# moduloAcionamento.net
KiCad netlist of a schematic drawn in EAGLE
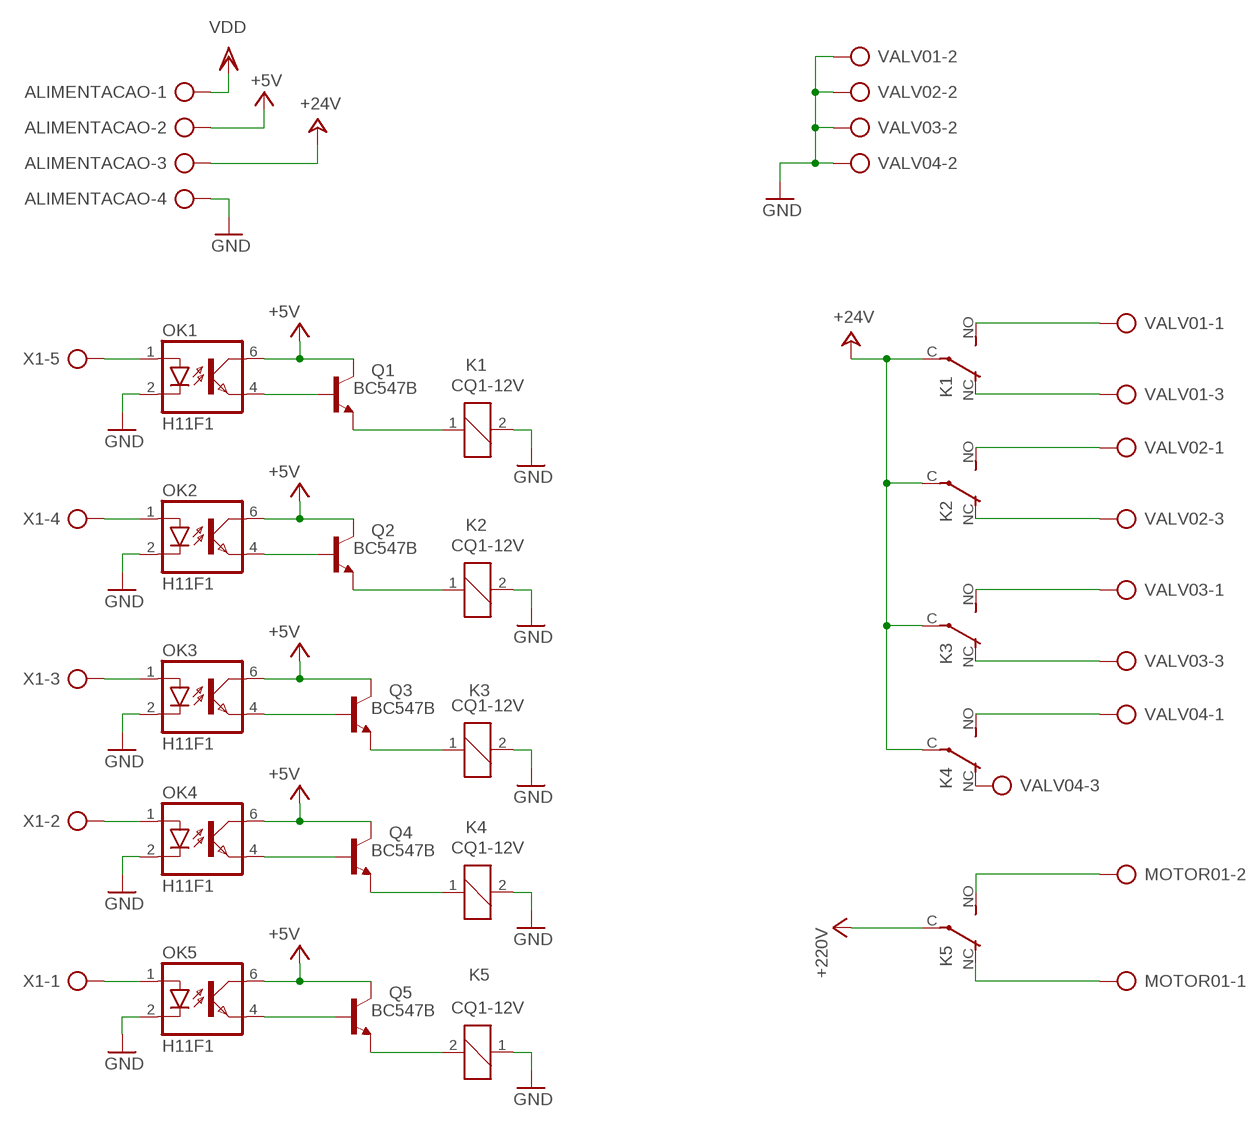
[diagram p0: schematic, sheet 1]

(export (version "E")
  (design (tool "Eeschema 10.0.6"))
  (components
    (comp (ref "ALIMENTACAO")
      (value "AK500/4")
      (footprint "eagle-import:AK500_4")
      (libsource (lib "eagle-import") (part "AK500/4"))
    )
    (comp (ref "K1")
      (value "CQ1-12V")
      (footprint "eagle-import:CQ1")
      (libsource (lib "eagle-import") (part "CQ1-12V"))
    )
    (comp (ref "K2")
      (value "CQ1-12V")
      (footprint "eagle-import:CQ1")
      (libsource (lib "eagle-import") (part "CQ1-12V"))
    )
    (comp (ref "K3")
      (value "CQ1-12V")
      (footprint "eagle-import:CQ1")
      (libsource (lib "eagle-import") (part "CQ1-12V"))
    )
    (comp (ref "K4")
      (value "CQ1-12V")
      (footprint "eagle-import:CQ1")
      (libsource (lib "eagle-import") (part "CQ1-12V"))
    )
    (comp (ref "K5")
      (value "CQ1-12V")
      (footprint "eagle-import:CQ1")
      (libsource (lib "eagle-import") (part "CQ1-12V"))
    )
    (comp (ref "MOTOR01")
      (value "AK500/2")
      (footprint "eagle-import:AK500_2")
      (libsource (lib "eagle-import") (part "AK500/2"))
    )
    (comp (ref "OK1")
      (value "H11F1")
      (footprint "eagle-import:DIL05")
      (libsource (lib "eagle-import") (part "H11F1"))
    )
    (comp (ref "OK2")
      (value "H11F1")
      (footprint "eagle-import:DIL05")
      (libsource (lib "eagle-import") (part "H11F1"))
    )
    (comp (ref "OK3")
      (value "H11F1")
      (footprint "eagle-import:DIL05")
      (libsource (lib "eagle-import") (part "H11F1"))
    )
    (comp (ref "OK4")
      (value "H11F1")
      (footprint "eagle-import:DIL05")
      (libsource (lib "eagle-import") (part "H11F1"))
    )
    (comp (ref "OK5")
      (value "H11F1")
      (footprint "eagle-import:DIL05")
      (libsource (lib "eagle-import") (part "H11F1"))
    )
    (comp (ref "Q1")
      (value "BC547B")
      (footprint "eagle-import:TO92")
      (libsource (lib "eagle-import") (part "BC547B"))
    )
    (comp (ref "Q2")
      (value "BC547B")
      (footprint "eagle-import:TO92")
      (libsource (lib "eagle-import") (part "BC547B"))
    )
    (comp (ref "Q3")
      (value "BC547B")
      (footprint "eagle-import:TO92")
      (libsource (lib "eagle-import") (part "BC547B"))
    )
    (comp (ref "Q4")
      (value "BC547B")
      (footprint "eagle-import:TO92")
      (libsource (lib "eagle-import") (part "BC547B"))
    )
    (comp (ref "Q5")
      (value "BC547B")
      (footprint "eagle-import:TO92")
      (libsource (lib "eagle-import") (part "BC547B"))
    )
    (comp (ref "VALV01")
      (value "AK500/3")
      (footprint "eagle-import:AK500_3")
      (libsource (lib "eagle-import") (part "AK500/3"))
    )
    (comp (ref "VALV02")
      (value "AK500/3")
      (footprint "eagle-import:AK500_3")
      (libsource (lib "eagle-import") (part "AK500/3"))
    )
    (comp (ref "VALV03")
      (value "AK500/3")
      (footprint "eagle-import:AK500_3")
      (libsource (lib "eagle-import") (part "AK500/3"))
    )
    (comp (ref "VALV04")
      (value "AK500/3")
      (footprint "eagle-import:AK500_3")
      (libsource (lib "eagle-import") (part "AK500/3"))
    )
    (comp (ref "X1")
      (value "AK500/5")
      (footprint "eagle-import:AK500_5")
      (libsource (lib "eagle-import") (part "AK500/5"))
    )
  )
  (nets
    (net (code "1") (name "+24V") (class "Default")
      (node (ref "ALIMENTACAO") (pin "3") (pinfunction "KL_3") (pintype "passive"))
      (node (ref "K1") (pin "C") (pinfunction "P_C") (pintype "passive"))
      (node (ref "K2") (pin "C") (pinfunction "P_C") (pintype "passive"))
      (node (ref "K3") (pin "C") (pinfunction "P_C") (pintype "passive"))
      (node (ref "K4") (pin "C") (pinfunction "P_C") (pintype "passive"))
    )
    (net (code "2") (name "+220V") (class "Default")
      (node (ref "ALIMENTACAO") (pin "2") (pinfunction "KL_2") (pintype "passive"))
      (node (ref "K5") (pin "C") (pinfunction "P_C") (pintype "passive"))
      (node (ref "OK1") (pin "6") (pinfunction "COL_6") (pintype "passive"))
      (node (ref "OK2") (pin "6") (pinfunction "COL_6") (pintype "passive"))
      (node (ref "OK3") (pin "6") (pinfunction "COL_6") (pintype "passive"))
      (node (ref "OK4") (pin "6") (pinfunction "COL_6") (pintype "passive"))
      (node (ref "OK5") (pin "6") (pinfunction "COL_6") (pintype "passive"))
      (node (ref "Q1") (pin "3") (pinfunction "C_3") (pintype "passive"))
      (node (ref "Q2") (pin "3") (pinfunction "C_3") (pintype "passive"))
      (node (ref "Q3") (pin "3") (pinfunction "C_3") (pintype "passive"))
      (node (ref "Q4") (pin "3") (pinfunction "C_3") (pintype "passive"))
      (node (ref "Q5") (pin "3") (pinfunction "C_3") (pintype "passive"))
    )
    (net (code "3") (name "GND") (class "Default")
      (node (ref "ALIMENTACAO") (pin "4") (pinfunction "KL_4") (pintype "passive"))
      (node (ref "K1") (pin "2") (pinfunction "2_2") (pintype "passive"))
      (node (ref "K2") (pin "2") (pinfunction "2_2") (pintype "passive"))
      (node (ref "K3") (pin "2") (pinfunction "2_2") (pintype "passive"))
      (node (ref "K4") (pin "2") (pinfunction "2_2") (pintype "passive"))
      (node (ref "K5") (pin "1") (pinfunction "1_1") (pintype "passive"))
      (node (ref "OK1") (pin "2") (pinfunction "C_2") (pintype "passive"))
      (node (ref "OK2") (pin "2") (pinfunction "C_2") (pintype "passive"))
      (node (ref "OK3") (pin "2") (pinfunction "C_2") (pintype "passive"))
      (node (ref "OK4") (pin "2") (pinfunction "C_2") (pintype "passive"))
      (node (ref "OK5") (pin "2") (pinfunction "C_2") (pintype "passive"))
      (node (ref "VALV01") (pin "2") (pinfunction "KL_2") (pintype "passive"))
      (node (ref "VALV02") (pin "2") (pinfunction "KL_2") (pintype "passive"))
      (node (ref "VALV03") (pin "2") (pinfunction "KL_2") (pintype "passive"))
      (node (ref "VALV04") (pin "2") (pinfunction "KL_2") (pintype "passive"))
    )
    (net (code "4") (name "Net-(K1B-O)") (class "Default")
      (node (ref "K1") (pin "NC") (pinfunction "O_NC") (pintype "passive"))
      (node (ref "VALV01") (pin "3") (pinfunction "KL_3") (pintype "passive"))
    )
    (net (code "5") (name "Net-(K1B-S)") (class "Default")
      (node (ref "K1") (pin "NO") (pinfunction "S_NO") (pintype "passive"))
      (node (ref "VALV01") (pin "1") (pinfunction "KL_1") (pintype "passive"))
    )
    (net (code "6") (name "Net-(K2B-O)") (class "Default")
      (node (ref "K2") (pin "NC") (pinfunction "O_NC") (pintype "passive"))
      (node (ref "VALV02") (pin "3") (pinfunction "KL_3") (pintype "passive"))
    )
    (net (code "7") (name "Net-(K2B-S)") (class "Default")
      (node (ref "K2") (pin "NO") (pinfunction "S_NO") (pintype "passive"))
      (node (ref "VALV02") (pin "1") (pinfunction "KL_1") (pintype "passive"))
    )
    (net (code "8") (name "Net-(K3B-O)") (class "Default")
      (node (ref "K3") (pin "NC") (pinfunction "O_NC") (pintype "passive"))
      (node (ref "VALV03") (pin "3") (pinfunction "KL_3") (pintype "passive"))
    )
    (net (code "9") (name "Net-(K3B-S)") (class "Default")
      (node (ref "K3") (pin "NO") (pinfunction "S_NO") (pintype "passive"))
      (node (ref "VALV03") (pin "1") (pinfunction "KL_1") (pintype "passive"))
    )
    (net (code "10") (name "Net-(K4B-O)") (class "Default")
      (node (ref "K4") (pin "NC") (pinfunction "O_NC") (pintype "passive"))
      (node (ref "VALV04") (pin "3") (pinfunction "KL_3") (pintype "passive"))
    )
    (net (code "11") (name "Net-(K4B-S)") (class "Default")
      (node (ref "K4") (pin "NO") (pinfunction "S_NO") (pintype "passive"))
      (node (ref "VALV04") (pin "1") (pinfunction "KL_1") (pintype "passive"))
    )
    (net (code "12") (name "Net-(K5B-O)") (class "Default")
      (node (ref "K5") (pin "NC") (pinfunction "O_NC") (pintype "passive"))
      (node (ref "MOTOR01") (pin "1") (pinfunction "KL_1") (pintype "passive"))
    )
    (net (code "13") (name "Net-(K5B-S)") (class "Default")
      (node (ref "K5") (pin "NO") (pinfunction "S_NO") (pintype "passive"))
      (node (ref "MOTOR01") (pin "2") (pinfunction "KL_2") (pintype "passive"))
    )
    (net (code "14") (name "Net-(OK1-A)") (class "Default")
      (node (ref "OK1") (pin "1") (pinfunction "A_1") (pintype "passive"))
      (node (ref "X1") (pin "5") (pinfunction "KL_5") (pintype "passive"))
    )
    (net (code "15") (name "Net-(OK1-EMIT)") (class "Default")
      (node (ref "OK1") (pin "4") (pinfunction "EMIT_4") (pintype "passive"))
      (node (ref "Q1") (pin "2") (pinfunction "B_2") (pintype "passive"))
    )
    (net (code "16") (name "Net-(OK2-A)") (class "Default")
      (node (ref "OK2") (pin "1") (pinfunction "A_1") (pintype "passive"))
      (node (ref "X1") (pin "4") (pinfunction "KL_4") (pintype "passive"))
    )
    (net (code "17") (name "Net-(OK2-EMIT)") (class "Default")
      (node (ref "OK2") (pin "4") (pinfunction "EMIT_4") (pintype "passive"))
      (node (ref "Q2") (pin "2") (pinfunction "B_2") (pintype "passive"))
    )
    (net (code "18") (name "Net-(OK3-A)") (class "Default")
      (node (ref "OK3") (pin "1") (pinfunction "A_1") (pintype "passive"))
      (node (ref "X1") (pin "3") (pinfunction "KL_3") (pintype "passive"))
    )
    (net (code "19") (name "Net-(OK3-EMIT)") (class "Default")
      (node (ref "OK3") (pin "4") (pinfunction "EMIT_4") (pintype "passive"))
      (node (ref "Q3") (pin "2") (pinfunction "B_2") (pintype "passive"))
    )
    (net (code "20") (name "Net-(OK4-A)") (class "Default")
      (node (ref "OK4") (pin "1") (pinfunction "A_1") (pintype "passive"))
      (node (ref "X1") (pin "2") (pinfunction "KL_2") (pintype "passive"))
    )
    (net (code "21") (name "Net-(OK4-EMIT)") (class "Default")
      (node (ref "OK4") (pin "4") (pinfunction "EMIT_4") (pintype "passive"))
      (node (ref "Q4") (pin "2") (pinfunction "B_2") (pintype "passive"))
    )
    (net (code "22") (name "Net-(OK5-A)") (class "Default")
      (node (ref "OK5") (pin "1") (pinfunction "A_1") (pintype "passive"))
      (node (ref "X1") (pin "1") (pinfunction "KL_1") (pintype "passive"))
    )
    (net (code "23") (name "Net-(OK5-EMIT)") (class "Default")
      (node (ref "OK5") (pin "4") (pinfunction "EMIT_4") (pintype "passive"))
      (node (ref "Q5") (pin "2") (pinfunction "B_2") (pintype "passive"))
    )
    (net (code "24") (name "Net-(Q1-E)") (class "Default")
      (node (ref "K1") (pin "1") (pinfunction "1_1") (pintype "passive"))
      (node (ref "Q1") (pin "1") (pinfunction "E_1") (pintype "passive"))
    )
    (net (code "25") (name "Net-(Q2-E)") (class "Default")
      (node (ref "K2") (pin "1") (pinfunction "1_1") (pintype "passive"))
      (node (ref "Q2") (pin "1") (pinfunction "E_1") (pintype "passive"))
    )
    (net (code "26") (name "Net-(Q3-E)") (class "Default")
      (node (ref "K3") (pin "1") (pinfunction "1_1") (pintype "passive"))
      (node (ref "Q3") (pin "1") (pinfunction "E_1") (pintype "passive"))
    )
    (net (code "27") (name "Net-(Q4-E)") (class "Default")
      (node (ref "K4") (pin "1") (pinfunction "1_1") (pintype "passive"))
      (node (ref "Q4") (pin "1") (pinfunction "E_1") (pintype "passive"))
    )
    (net (code "28") (name "Net-(Q5-E)") (class "Default")
      (node (ref "K5") (pin "2") (pinfunction "2_2") (pintype "passive"))
      (node (ref "Q5") (pin "1") (pinfunction "E_1") (pintype "passive"))
    )
    (net (code "29") (name "VDD") (class "Default")
      (node (ref "ALIMENTACAO") (pin "1") (pinfunction "KL_1") (pintype "passive"))
    )
  )
)
